# BleShield.net
KiCad netlist of a schematic drawn in EAGLE
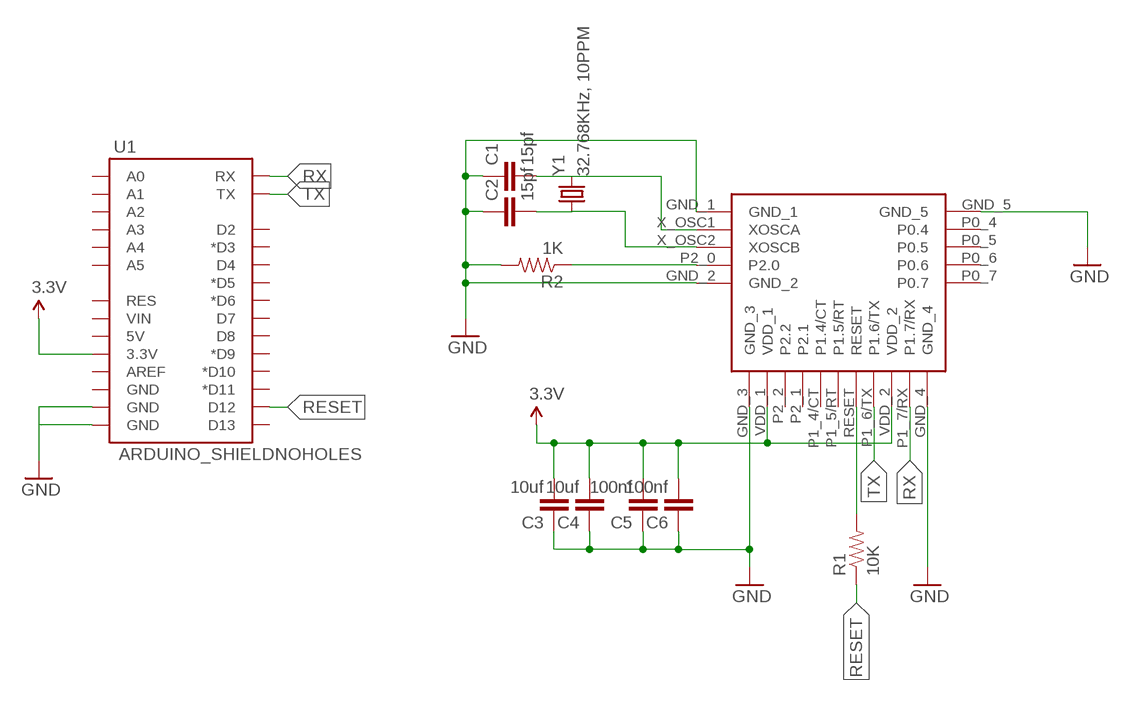
[diagram p0: schematic, sheet 1]

(export (version "E")
  (design (tool "Eeschema 10.0.6"))
  (components
    (comp (ref "C1")
      (value "15pf")
      (footprint "eagle-import:0805")
      (libsource (lib "eagle-import") (part "CAP0805"))
    )
    (comp (ref "C2")
      (value "15pf")
      (footprint "eagle-import:0805")
      (libsource (lib "eagle-import") (part "CAP0805"))
    )
    (comp (ref "C3")
      (value "10uf")
      (footprint "eagle-import:0805")
      (libsource (lib "eagle-import") (part "CAP0805"))
    )
    (comp (ref "C4")
      (value "10uf")
      (footprint "eagle-import:0805")
      (libsource (lib "eagle-import") (part "CAP0805"))
    )
    (comp (ref "C5")
      (value "100nf")
      (footprint "eagle-import:0805")
      (libsource (lib "eagle-import") (part "CAP0805"))
    )
    (comp (ref "C6")
      (value "100nf")
      (footprint "eagle-import:0805")
      (libsource (lib "eagle-import") (part "CAP0805"))
    )
    (comp (ref "R1")
      (value "10K")
      (footprint "eagle-import:0805")
      (libsource (lib "eagle-import") (part "RESISTOR0805-RES"))
    )
    (comp (ref "R2")
      (value "1K")
      (footprint "eagle-import:0805")
      (libsource (lib "eagle-import") (part "RESISTOR0805-RES"))
    )
    (comp (ref "U$1")
      (value "BG213L")
      (footprint "eagle-import:BG312L")
      (libsource (lib "eagle-import") (part "BG213L"))
    )
    (comp (ref "U1")
      (value "ARDUINO_SHIELDNOHOLES")
      (footprint "eagle-import:DUEMILANOVE_SHIELD_NOHOLES")
      (libsource (lib "eagle-import") (part "ARDUINO_SHIELDNOHOLES"))
    )
    (comp (ref "Y1")
      (value "32.768KHz, 10PPM")
      (footprint "eagle-import:CRYSTAL-32KHZ-SMD")
      (libsource (lib "eagle-import") (part "CRYSTAL32-SMD"))
    )
  )
  (nets
    (net (code "1") (name "3.3V") (class "Default")
      (node (ref "C3") (pin "2") (pinfunction "2_2") (pintype "passive"))
      (node (ref "C4") (pin "2") (pinfunction "2_2") (pintype "passive"))
      (node (ref "C5") (pin "2") (pinfunction "2_2") (pintype "passive"))
      (node (ref "C6") (pin "2") (pinfunction "2_2") (pintype "passive"))
      (node (ref "U$1") (pin "VDD_1") (pinfunction "VDD_1_VDD_1") (pintype "bidirectional"))
      (node (ref "U$1") (pin "VDD_2") (pinfunction "VDD_2_VDD_2") (pintype "bidirectional"))
      (node (ref "U1") (pin "3.3V") (pinfunction "3.3V_3.3V") (pintype "bidirectional"))
    )
    (net (code "2") (name "GND") (class "Default")
      (node (ref "C1") (pin "1") (pinfunction "1_1") (pintype "passive"))
      (node (ref "C2") (pin "1") (pinfunction "1_1") (pintype "passive"))
      (node (ref "C3") (pin "1") (pinfunction "1_1") (pintype "passive"))
      (node (ref "C4") (pin "1") (pinfunction "1_1") (pintype "passive"))
      (node (ref "C5") (pin "1") (pinfunction "1_1") (pintype "passive"))
      (node (ref "C6") (pin "1") (pinfunction "1_1") (pintype "passive"))
      (node (ref "R2") (pin "2") (pinfunction "2_2") (pintype "passive"))
      (node (ref "U$1") (pin "GND_1") (pinfunction "GND_1_GND_1") (pintype "bidirectional"))
      (node (ref "U$1") (pin "GND_2") (pinfunction "GND_2_GND_2") (pintype "bidirectional"))
      (node (ref "U$1") (pin "GND_3") (pinfunction "GND_3_GND_3") (pintype "bidirectional"))
      (node (ref "U$1") (pin "GND_4") (pinfunction "GND_4_GND_4") (pintype "bidirectional"))
      (node (ref "U$1") (pin "GND_5") (pinfunction "GND_5_GND_5") (pintype "bidirectional"))
      (node (ref "U1") (pin "GND@0") (pinfunction "GND_GND@0") (pintype "bidirectional"))
      (node (ref "U1") (pin "GND@1") (pinfunction "GND_GND@1") (pintype "bidirectional"))
    )
    (net (code "3") (name "Net-(R1-Pad2)") (class "Default")
      (node (ref "R1") (pin "2") (pinfunction "2_2") (pintype "passive"))
      (node (ref "U$1") (pin "RESET") (pinfunction "RESET_RESET") (pintype "bidirectional"))
    )
    (net (code "4") (name "Net-(U$1-P2.0)") (class "Default")
      (node (ref "R2") (pin "1") (pinfunction "1_1") (pintype "passive"))
      (node (ref "U$1") (pin "P2_0") (pinfunction "P2.0_P2_0") (pintype "bidirectional"))
    )
    (net (code "5") (name "Net-(U$1-XOSCA)") (class "Default")
      (node (ref "C1") (pin "2") (pinfunction "2_2") (pintype "passive"))
      (node (ref "U$1") (pin "X_OSC1") (pinfunction "XOSCA_X_OSC1") (pintype "bidirectional"))
      (node (ref "Y1") (pin "X2") (pinfunction "2_X2") (pintype "passive"))
    )
    (net (code "6") (name "Net-(U$1-XOSCB)") (class "Default")
      (node (ref "C2") (pin "2") (pinfunction "2_2") (pintype "passive"))
      (node (ref "U$1") (pin "X_OSC2") (pinfunction "XOSCB_X_OSC2") (pintype "bidirectional"))
      (node (ref "Y1") (pin "X1") (pinfunction "1_X1") (pintype "passive"))
    )
    (net (code "7") (name "RESET") (class "Default")
      (node (ref "R1") (pin "1") (pinfunction "1_1") (pintype "passive"))
      (node (ref "U1") (pin "D12") (pinfunction "D12_D12") (pintype "bidirectional"))
    )
    (net (code "8") (name "RX") (class "Default")
      (node (ref "U$1") (pin "P1_7/RX") (pinfunction "P1.7/RX_P1_7/RX") (pintype "bidirectional"))
      (node (ref "U1") (pin "RX") (pinfunction "RX_RX") (pintype "bidirectional"))
    )
    (net (code "9") (name "TX") (class "Default")
      (node (ref "U$1") (pin "P1_6/TX") (pinfunction "P1.6/TX_P1_6/TX") (pintype "bidirectional"))
      (node (ref "U1") (pin "TX") (pinfunction "TX_TX") (pintype "bidirectional"))
    )
    (net (code "10") (name "unconnected-(U$1-P0.4-PadP0_4)") (class "Default")
      (node (ref "U$1") (pin "P0_4") (pinfunction "P0.4_P0_4") (pintype "bidirectional"))
    )
    (net (code "11") (name "unconnected-(U$1-P0.5-PadP0_5)") (class "Default")
      (node (ref "U$1") (pin "P0_5") (pinfunction "P0.5_P0_5") (pintype "bidirectional"))
    )
    (net (code "12") (name "unconnected-(U$1-P0.6-PadP0_6)") (class "Default")
      (node (ref "U$1") (pin "P0_6") (pinfunction "P0.6_P0_6") (pintype "bidirectional"))
    )
    (net (code "13") (name "unconnected-(U$1-P0.7-PadP0_7)") (class "Default")
      (node (ref "U$1") (pin "P0_7") (pinfunction "P0.7_P0_7") (pintype "bidirectional"))
    )
    (net (code "14") (name "unconnected-(U$1-P1.4{slash}CT-PadP1_4{slash}CT)") (class "Default")
      (node (ref "U$1") (pin "P1_4/CT") (pinfunction "P1.4/CT_P1_4/CT") (pintype "bidirectional"))
    )
    (net (code "15") (name "unconnected-(U$1-P1.5{slash}RT-PadP1_5{slash}RT)") (class "Default")
      (node (ref "U$1") (pin "P1_5/RT") (pinfunction "P1.5/RT_P1_5/RT") (pintype "bidirectional"))
    )
    (net (code "16") (name "unconnected-(U$1-P2.1-PadP2_1)") (class "Default")
      (node (ref "U$1") (pin "P2_1") (pinfunction "P2.1_P2_1") (pintype "bidirectional"))
    )
    (net (code "17") (name "unconnected-(U$1-P2.2-PadP2_2)") (class "Default")
      (node (ref "U$1") (pin "P2_2") (pinfunction "P2.2_P2_2") (pintype "bidirectional"))
    )
    (net (code "18") (name "unconnected-(U1-*D3-PadD3)") (class "Default")
      (node (ref "U1") (pin "D3") (pinfunction "*D3_D3") (pintype "bidirectional"))
    )
    (net (code "19") (name "unconnected-(U1-*D5-PadD5)") (class "Default")
      (node (ref "U1") (pin "D5") (pinfunction "*D5_D5") (pintype "bidirectional"))
    )
    (net (code "20") (name "unconnected-(U1-*D6-PadD6)") (class "Default")
      (node (ref "U1") (pin "D6") (pinfunction "*D6_D6") (pintype "bidirectional"))
    )
    (net (code "21") (name "unconnected-(U1-*D9-PadD9)") (class "Default")
      (node (ref "U1") (pin "D9") (pinfunction "*D9_D9") (pintype "bidirectional"))
    )
    (net (code "22") (name "unconnected-(U1-*D10-PadD10)") (class "Default")
      (node (ref "U1") (pin "D10") (pinfunction "*D10_D10") (pintype "bidirectional"))
    )
    (net (code "23") (name "unconnected-(U1-*D11-PadD11)") (class "Default")
      (node (ref "U1") (pin "D11") (pinfunction "*D11_D11") (pintype "bidirectional"))
    )
    (net (code "24") (name "unconnected-(U1-GND-PadGND@2)") (class "Default")
      (node (ref "U1") (pin "GND@2") (pinfunction "GND_GND@2") (pintype "bidirectional"))
    )
    (net (code "25") (name "unconnected-(U1-Pad5V)") (class "Default")
      (node (ref "U1") (pin "5V") (pinfunction "5V_5V") (pintype "bidirectional"))
    )
    (net (code "26") (name "unconnected-(U1-PadA0)") (class "Default")
      (node (ref "U1") (pin "A0") (pinfunction "A0_A0") (pintype "bidirectional"))
    )
    (net (code "27") (name "unconnected-(U1-PadA1)") (class "Default")
      (node (ref "U1") (pin "A1") (pinfunction "A1_A1") (pintype "bidirectional"))
    )
    (net (code "28") (name "unconnected-(U1-PadA2)") (class "Default")
      (node (ref "U1") (pin "A2") (pinfunction "A2_A2") (pintype "bidirectional"))
    )
    (net (code "29") (name "unconnected-(U1-PadA3)") (class "Default")
      (node (ref "U1") (pin "A3") (pinfunction "A3_A3") (pintype "bidirectional"))
    )
    (net (code "30") (name "unconnected-(U1-PadA4)") (class "Default")
      (node (ref "U1") (pin "A4") (pinfunction "A4_A4") (pintype "bidirectional"))
    )
    (net (code "31") (name "unconnected-(U1-PadA5)") (class "Default")
      (node (ref "U1") (pin "A5") (pinfunction "A5_A5") (pintype "bidirectional"))
    )
    (net (code "32") (name "unconnected-(U1-PadAREF)") (class "Default")
      (node (ref "U1") (pin "AREF") (pinfunction "AREF_AREF") (pintype "bidirectional"))
    )
    (net (code "33") (name "unconnected-(U1-PadD2)") (class "Default")
      (node (ref "U1") (pin "D2") (pinfunction "D2_D2") (pintype "bidirectional"))
    )
    (net (code "34") (name "unconnected-(U1-PadD4)") (class "Default")
      (node (ref "U1") (pin "D4") (pinfunction "D4_D4") (pintype "bidirectional"))
    )
    (net (code "35") (name "unconnected-(U1-PadD7)") (class "Default")
      (node (ref "U1") (pin "D7") (pinfunction "D7_D7") (pintype "bidirectional"))
    )
    (net (code "36") (name "unconnected-(U1-PadD8)") (class "Default")
      (node (ref "U1") (pin "D8") (pinfunction "D8_D8") (pintype "bidirectional"))
    )
    (net (code "37") (name "unconnected-(U1-PadD13)") (class "Default")
      (node (ref "U1") (pin "D13") (pinfunction "D13_D13") (pintype "bidirectional"))
    )
    (net (code "38") (name "unconnected-(U1-PadRES)") (class "Default")
      (node (ref "U1") (pin "RES") (pinfunction "RES_RES") (pintype "bidirectional"))
    )
    (net (code "39") (name "unconnected-(U1-PadVIN)") (class "Default")
      (node (ref "U1") (pin "VIN") (pinfunction "VIN_VIN") (pintype "bidirectional"))
    )
  )
)
